# simpleArm-1.net
KiCad netlist of a schematic drawn in EAGLE
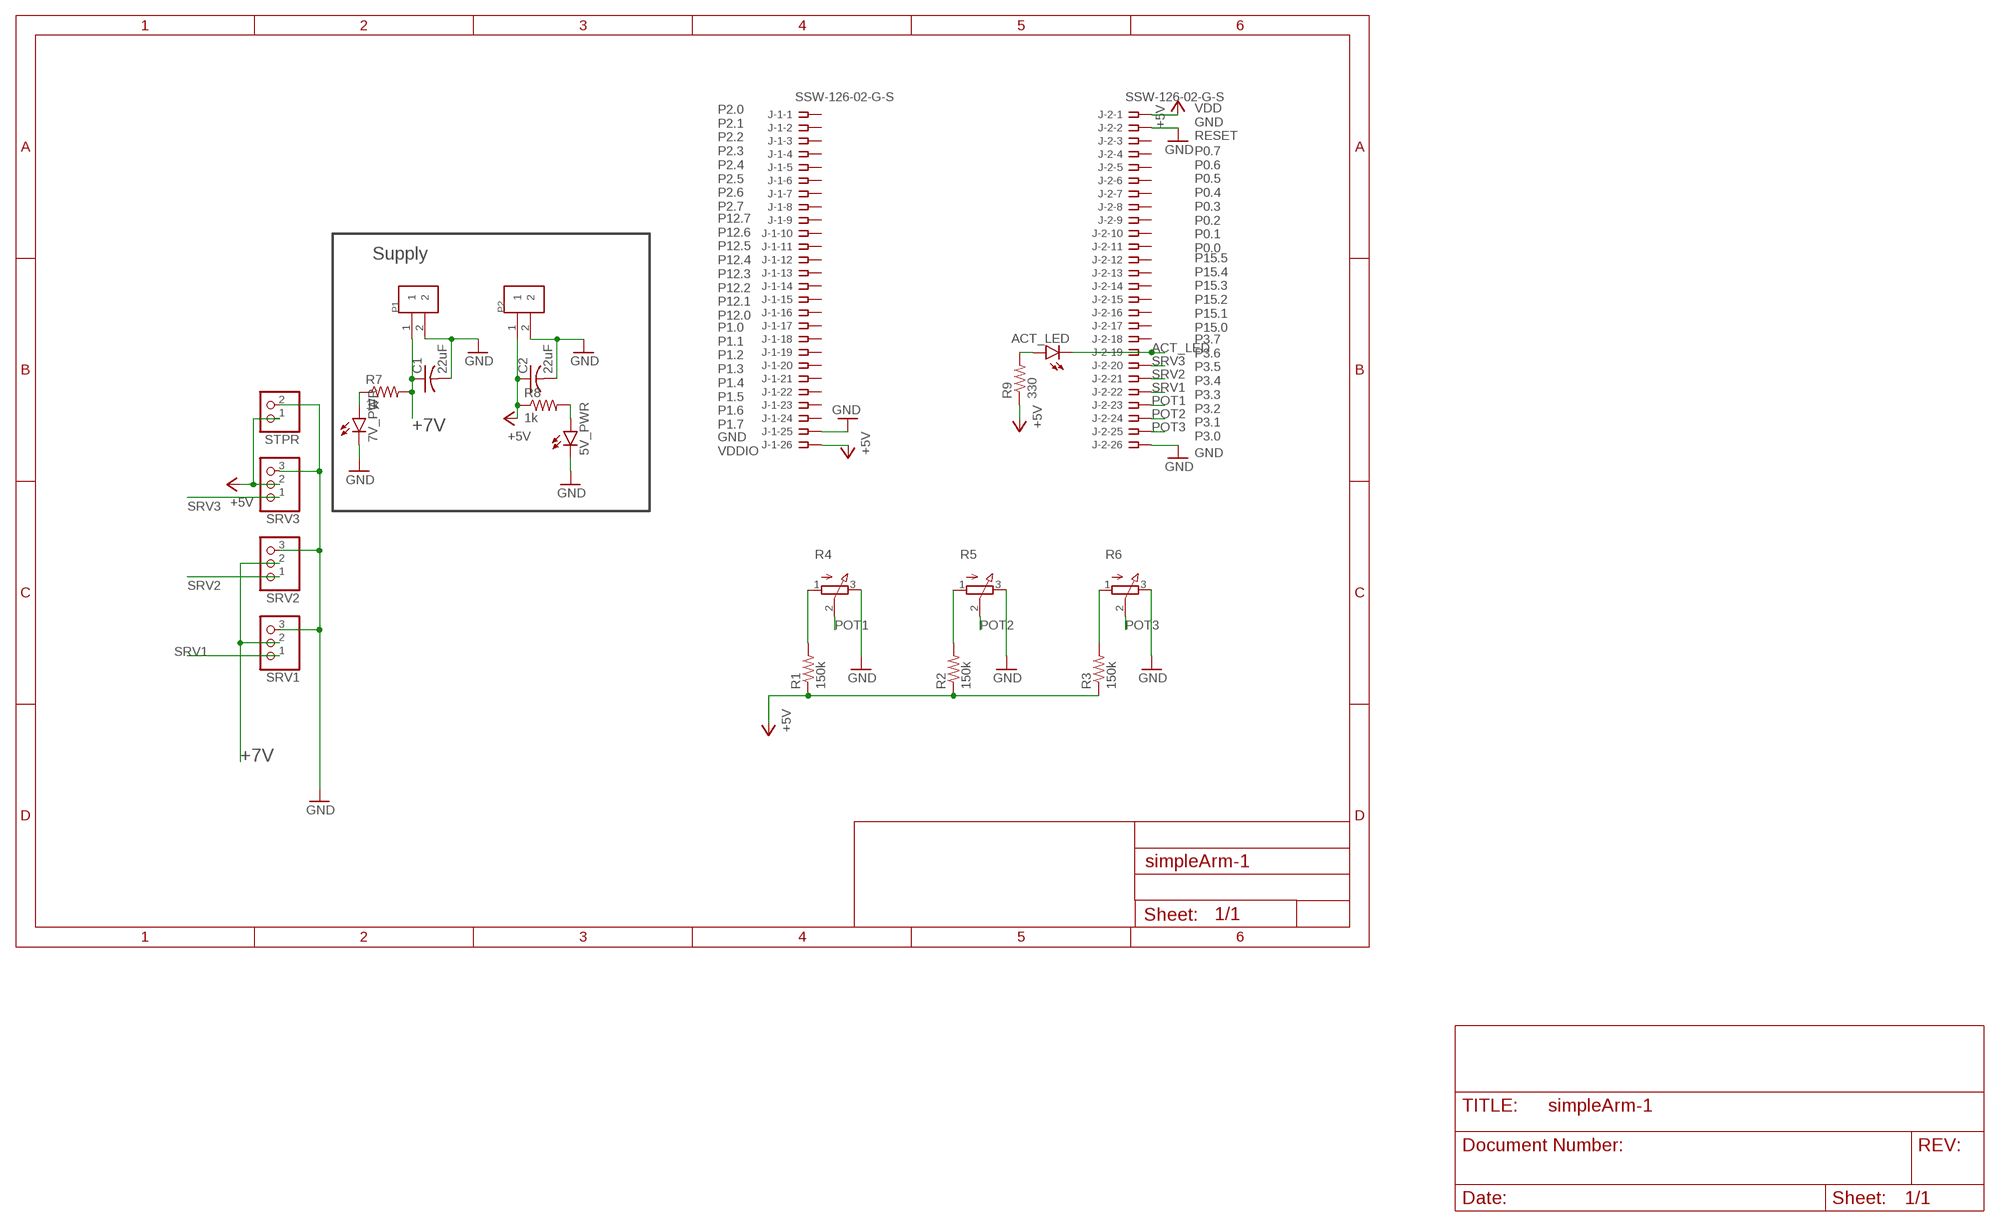
[diagram p0: schematic, sheet 1]

(export (version "E")
  (design (tool "Eeschema 10.0.6"))
  (components
    (comp (ref "5V_PWR")
      (value "LED3MM")
      (footprint "eagle-import:LED3MM")
      (libsource (lib "eagle-import") (part "LED3MM"))
    )
    (comp (ref "7V_PWR")
      (value "LED3MM")
      (footprint "eagle-import:LED3MM")
      (libsource (lib "eagle-import") (part "LED3MM"))
    )
    (comp (ref "ACT_LED")
      (value "LED3MM")
      (footprint "eagle-import:LED3MM")
      (libsource (lib "eagle-import") (part "LED3MM"))
    )
    (comp (ref "C1")
      (value "22uF")
      (footprint "eagle-import:C050-030X075")
      (libsource (lib "eagle-import") (part "C-US050-030X075"))
    )
    (comp (ref "C2")
      (value "22uF")
      (footprint "eagle-import:C050-030X075")
      (libsource (lib "eagle-import") (part "C-US050-030X075"))
    )
    (comp (ref "J-1")
      (value "SSW-126-02-G-S")
      (footprint "eagle-import:SSW-126-02-G-S")
      (fields (field (name "MF") "Samtec Inc."))
      (libsource (lib "eagle-import") (part "SSW-126-02-G-S"))
    )
    (comp (ref "J-2")
      (value "SSW-126-02-G-S")
      (footprint "eagle-import:SSW-126-02-G-S")
      (fields (field (name "MF") "Samtec Inc."))
      (libsource (lib "eagle-import") (part "SSW-126-02-G-S"))
    )
    (comp (ref "P1")
      (value "282837-2")
      (footprint "eagle-import:TE_282837-2")
      (fields (field (name "MF") "TE Connectivity"))
      (libsource (lib "eagle-import") (part "282837-2"))
    )
    (comp (ref "P2")
      (value "282837-2")
      (footprint "eagle-import:TE_282837-2")
      (fields (field (name "MF") "TE Connectivity"))
      (libsource (lib "eagle-import") (part "282837-2"))
    )
    (comp (ref "R1")
      (value "150k")
      (footprint "eagle-import:0204_7")
      (libsource (lib "eagle-import") (part "R-US_0204/7"))
    )
    (comp (ref "R2")
      (value "150k")
      (footprint "eagle-import:0204_7")
      (libsource (lib "eagle-import") (part "R-US_0204/7"))
    )
    (comp (ref "R3")
      (value "150k")
      (footprint "eagle-import:0204_7")
      (libsource (lib "eagle-import") (part "R-US_0204/7"))
    )
    (comp (ref "R4")
      (value "3RP/1610N")
      (footprint "eagle-import:3RP_1610N")
      (libsource (lib "eagle-import") (part "3RP/1610N"))
    )
    (comp (ref "R5")
      (value "3RP/1610N")
      (footprint "eagle-import:3RP_1610N")
      (libsource (lib "eagle-import") (part "3RP/1610N"))
    )
    (comp (ref "R6")
      (value "3RP/1610N")
      (footprint "eagle-import:3RP_1610N")
      (libsource (lib "eagle-import") (part "3RP/1610N"))
    )
    (comp (ref "R7")
      (value "1k")
      (footprint "eagle-import:0204_7")
      (libsource (lib "eagle-import") (part "R-US_0204/7"))
    )
    (comp (ref "R8")
      (value "1k")
      (footprint "eagle-import:0204_7")
      (libsource (lib "eagle-import") (part "R-US_0204/7"))
    )
    (comp (ref "R9")
      (value "330")
      (footprint "eagle-import:0204_7")
      (libsource (lib "eagle-import") (part "R-US_0204/7"))
    )
    (comp (ref "SRV1")
      (value "PINHD-1X3")
      (footprint "eagle-import:1X03")
      (libsource (lib "eagle-import") (part "PINHD-1X3"))
    )
    (comp (ref "SRV2")
      (value "PINHD-1X3")
      (footprint "eagle-import:1X03")
      (libsource (lib "eagle-import") (part "PINHD-1X3"))
    )
    (comp (ref "SRV3")
      (value "PINHD-1X3")
      (footprint "eagle-import:1X03")
      (libsource (lib "eagle-import") (part "PINHD-1X3"))
    )
    (comp (ref "STPR")
      (value "PINHD-1X2")
      (footprint "eagle-import:1X02")
      (libsource (lib "eagle-import") (part "PINHD-1X2"))
    )
  )
  (nets
    (net (code "1") (name "+5V") (class "Default")
      (node (ref "C2") (pin "1") (pinfunction "1_1") (pintype "passive"))
      (node (ref "J-1") (pin "26") (pinfunction "1_26") (pintype "passive"))
      (node (ref "J-2") (pin "1") (pinfunction "1_1") (pintype "passive"))
      (node (ref "P2") (pin "1") (pinfunction "1_1") (pintype "passive"))
      (node (ref "R1") (pin "1") (pinfunction "1_1") (pintype "passive"))
      (node (ref "R2") (pin "1") (pinfunction "1_1") (pintype "passive"))
      (node (ref "R3") (pin "1") (pinfunction "1_1") (pintype "passive"))
      (node (ref "R8") (pin "1") (pinfunction "1_1") (pintype "passive"))
      (node (ref "R9") (pin "1") (pinfunction "1_1") (pintype "passive"))
      (node (ref "SRV3") (pin "2") (pinfunction "2_2") (pintype "passive"))
      (node (ref "STPR") (pin "1") (pinfunction "1_1") (pintype "passive"))
    )
    (net (code "2") (name "/+7V") (class "Default")
      (node (ref "C1") (pin "1") (pinfunction "1_1") (pintype "passive"))
      (node (ref "P1") (pin "1") (pinfunction "1_1") (pintype "passive"))
      (node (ref "R7") (pin "2") (pinfunction "2_2") (pintype "passive"))
      (node (ref "SRV1") (pin "2") (pinfunction "2_2") (pintype "passive"))
      (node (ref "SRV2") (pin "2") (pinfunction "2_2") (pintype "passive"))
    )
    (net (code "3") (name "/ACT_LED") (class "Default")
      (node (ref "ACT_LED") (pin "K") (pinfunction "C_K") (pintype "passive"))
      (node (ref "J-2") (pin "19") (pinfunction "1_19") (pintype "passive"))
    )
    (net (code "4") (name "/POT1") (class "Default")
      (node (ref "J-2") (pin "23") (pinfunction "1_23") (pintype "passive"))
      (node (ref "R4") (pin "2") (pinfunction "S_2") (pintype "passive"))
    )
    (net (code "5") (name "/POT2") (class "Default")
      (node (ref "J-2") (pin "24") (pinfunction "1_24") (pintype "passive"))
      (node (ref "R5") (pin "2") (pinfunction "S_2") (pintype "passive"))
    )
    (net (code "6") (name "/POT3") (class "Default")
      (node (ref "J-2") (pin "25") (pinfunction "1_25") (pintype "passive"))
      (node (ref "R6") (pin "2") (pinfunction "S_2") (pintype "passive"))
    )
    (net (code "7") (name "/SRV1") (class "Default")
      (node (ref "J-2") (pin "22") (pinfunction "1_22") (pintype "passive"))
      (node (ref "SRV1") (pin "1") (pinfunction "1_1") (pintype "passive"))
    )
    (net (code "8") (name "/SRV2") (class "Default")
      (node (ref "J-2") (pin "21") (pinfunction "1_21") (pintype "passive"))
      (node (ref "SRV2") (pin "1") (pinfunction "1_1") (pintype "passive"))
    )
    (net (code "9") (name "/SRV3") (class "Default")
      (node (ref "J-2") (pin "20") (pinfunction "1_20") (pintype "passive"))
      (node (ref "SRV3") (pin "1") (pinfunction "1_1") (pintype "passive"))
    )
    (net (code "10") (name "GND") (class "Default")
      (node (ref "5V_PWR") (pin "K") (pinfunction "C_K") (pintype "passive"))
      (node (ref "7V_PWR") (pin "K") (pinfunction "C_K") (pintype "passive"))
      (node (ref "C1") (pin "2") (pinfunction "2_2") (pintype "passive"))
      (node (ref "C2") (pin "2") (pinfunction "2_2") (pintype "passive"))
      (node (ref "J-1") (pin "25") (pinfunction "1_25") (pintype "passive"))
      (node (ref "J-2") (pin "2") (pinfunction "1_2") (pintype "passive"))
      (node (ref "J-2") (pin "26") (pinfunction "1_26") (pintype "passive"))
      (node (ref "P1") (pin "2") (pinfunction "2_2") (pintype "passive"))
      (node (ref "P2") (pin "2") (pinfunction "2_2") (pintype "passive"))
      (node (ref "R4") (pin "3") (pinfunction "E_3") (pintype "passive"))
      (node (ref "R5") (pin "3") (pinfunction "E_3") (pintype "passive"))
      (node (ref "R6") (pin "3") (pinfunction "E_3") (pintype "passive"))
      (node (ref "SRV1") (pin "3") (pinfunction "3_3") (pintype "passive"))
      (node (ref "SRV2") (pin "3") (pinfunction "3_3") (pintype "passive"))
      (node (ref "SRV3") (pin "3") (pinfunction "3_3") (pintype "passive"))
      (node (ref "STPR") (pin "2") (pinfunction "2_2") (pintype "passive"))
    )
    (net (code "11") (name "Net-(5V_PWR-PadA)") (class "Default")
      (node (ref "5V_PWR") (pin "A") (pinfunction "A_A") (pintype "passive"))
      (node (ref "R8") (pin "2") (pinfunction "2_2") (pintype "passive"))
    )
    (net (code "12") (name "Net-(7V_PWR-PadA)") (class "Default")
      (node (ref "7V_PWR") (pin "A") (pinfunction "A_A") (pintype "passive"))
      (node (ref "R7") (pin "1") (pinfunction "1_1") (pintype "passive"))
    )
    (net (code "13") (name "Net-(ACT_LED-PadA)") (class "Default")
      (node (ref "ACT_LED") (pin "A") (pinfunction "A_A") (pintype "passive"))
      (node (ref "R9") (pin "2") (pinfunction "2_2") (pintype "passive"))
    )
    (net (code "14") (name "Net-(R4-A)") (class "Default")
      (node (ref "R1") (pin "2") (pinfunction "2_2") (pintype "passive"))
      (node (ref "R4") (pin "1") (pinfunction "A_1") (pintype "passive"))
    )
    (net (code "15") (name "Net-(R5-A)") (class "Default")
      (node (ref "R2") (pin "2") (pinfunction "2_2") (pintype "passive"))
      (node (ref "R5") (pin "1") (pinfunction "A_1") (pintype "passive"))
    )
    (net (code "16") (name "Net-(R6-A)") (class "Default")
      (node (ref "R3") (pin "2") (pinfunction "2_2") (pintype "passive"))
      (node (ref "R6") (pin "1") (pinfunction "A_1") (pintype "passive"))
    )
    (net (code "17") (name "unconnected-(J-1-Pad1)") (class "Default")
      (node (ref "J-1") (pin "1") (pinfunction "1_1") (pintype "passive"))
    )
    (net (code "18") (name "unconnected-(J-1B-1-Pad10)") (class "Default")
      (node (ref "J-1") (pin "10") (pinfunction "1_10") (pintype "passive"))
    )
    (net (code "19") (name "unconnected-(J-1C-1-Pad11)") (class "Default")
      (node (ref "J-1") (pin "11") (pinfunction "1_11") (pintype "passive"))
    )
    (net (code "20") (name "unconnected-(J-1D-1-Pad12)") (class "Default")
      (node (ref "J-1") (pin "12") (pinfunction "1_12") (pintype "passive"))
    )
    (net (code "21") (name "unconnected-(J-1E-1-Pad13)") (class "Default")
      (node (ref "J-1") (pin "13") (pinfunction "1_13") (pintype "passive"))
    )
    (net (code "22") (name "unconnected-(J-1F-1-Pad14)") (class "Default")
      (node (ref "J-1") (pin "14") (pinfunction "1_14") (pintype "passive"))
    )
    (net (code "23") (name "unconnected-(J-1G-1-Pad15)") (class "Default")
      (node (ref "J-1") (pin "15") (pinfunction "1_15") (pintype "passive"))
    )
    (net (code "24") (name "unconnected-(J-1H-1-Pad16)") (class "Default")
      (node (ref "J-1") (pin "16") (pinfunction "1_16") (pintype "passive"))
    )
    (net (code "25") (name "unconnected-(J-1I-1-Pad17)") (class "Default")
      (node (ref "J-1") (pin "17") (pinfunction "1_17") (pintype "passive"))
    )
    (net (code "26") (name "unconnected-(J-1J-1-Pad18)") (class "Default")
      (node (ref "J-1") (pin "18") (pinfunction "1_18") (pintype "passive"))
    )
    (net (code "27") (name "unconnected-(J-1K-1-Pad19)") (class "Default")
      (node (ref "J-1") (pin "19") (pinfunction "1_19") (pintype "passive"))
    )
    (net (code "28") (name "unconnected-(J-1L-1-Pad2)") (class "Default")
      (node (ref "J-1") (pin "2") (pinfunction "1_2") (pintype "passive"))
    )
    (net (code "29") (name "unconnected-(J-1M-1-Pad20)") (class "Default")
      (node (ref "J-1") (pin "20") (pinfunction "1_20") (pintype "passive"))
    )
    (net (code "30") (name "unconnected-(J-1N-1-Pad21)") (class "Default")
      (node (ref "J-1") (pin "21") (pinfunction "1_21") (pintype "passive"))
    )
    (net (code "31") (name "unconnected-(J-1O-1-Pad22)") (class "Default")
      (node (ref "J-1") (pin "22") (pinfunction "1_22") (pintype "passive"))
    )
    (net (code "32") (name "unconnected-(J-1P-1-Pad23)") (class "Default")
      (node (ref "J-1") (pin "23") (pinfunction "1_23") (pintype "passive"))
    )
    (net (code "33") (name "unconnected-(J-1Q-1-Pad24)") (class "Default")
      (node (ref "J-1") (pin "24") (pinfunction "1_24") (pintype "passive"))
    )
    (net (code "34") (name "unconnected-(J-1T-1-Pad3)") (class "Default")
      (node (ref "J-1") (pin "3") (pinfunction "1_3") (pintype "passive"))
    )
    (net (code "35") (name "unconnected-(J-1U-1-Pad4)") (class "Default")
      (node (ref "J-1") (pin "4") (pinfunction "1_4") (pintype "passive"))
    )
    (net (code "36") (name "unconnected-(J-1V-1-Pad5)") (class "Default")
      (node (ref "J-1") (pin "5") (pinfunction "1_5") (pintype "passive"))
    )
    (net (code "37") (name "unconnected-(J-1W-1-Pad6)") (class "Default")
      (node (ref "J-1") (pin "6") (pinfunction "1_6") (pintype "passive"))
    )
    (net (code "38") (name "unconnected-(J-1X-1-Pad7)") (class "Default")
      (node (ref "J-1") (pin "7") (pinfunction "1_7") (pintype "passive"))
    )
    (net (code "39") (name "unconnected-(J-1Y-1-Pad8)") (class "Default")
      (node (ref "J-1") (pin "8") (pinfunction "1_8") (pintype "passive"))
    )
    (net (code "40") (name "unconnected-(J-1Z-1-Pad9)") (class "Default")
      (node (ref "J-1") (pin "9") (pinfunction "1_9") (pintype "passive"))
    )
    (net (code "41") (name "unconnected-(J-2B-1-Pad10)") (class "Default")
      (node (ref "J-2") (pin "10") (pinfunction "1_10") (pintype "passive"))
    )
    (net (code "42") (name "unconnected-(J-2C-1-Pad11)") (class "Default")
      (node (ref "J-2") (pin "11") (pinfunction "1_11") (pintype "passive"))
    )
    (net (code "43") (name "unconnected-(J-2D-1-Pad12)") (class "Default")
      (node (ref "J-2") (pin "12") (pinfunction "1_12") (pintype "passive"))
    )
    (net (code "44") (name "unconnected-(J-2E-1-Pad13)") (class "Default")
      (node (ref "J-2") (pin "13") (pinfunction "1_13") (pintype "passive"))
    )
    (net (code "45") (name "unconnected-(J-2F-1-Pad14)") (class "Default")
      (node (ref "J-2") (pin "14") (pinfunction "1_14") (pintype "passive"))
    )
    (net (code "46") (name "unconnected-(J-2G-1-Pad15)") (class "Default")
      (node (ref "J-2") (pin "15") (pinfunction "1_15") (pintype "passive"))
    )
    (net (code "47") (name "unconnected-(J-2H-1-Pad16)") (class "Default")
      (node (ref "J-2") (pin "16") (pinfunction "1_16") (pintype "passive"))
    )
    (net (code "48") (name "unconnected-(J-2I-1-Pad17)") (class "Default")
      (node (ref "J-2") (pin "17") (pinfunction "1_17") (pintype "passive"))
    )
    (net (code "49") (name "unconnected-(J-2J-1-Pad18)") (class "Default")
      (node (ref "J-2") (pin "18") (pinfunction "1_18") (pintype "passive"))
    )
    (net (code "50") (name "unconnected-(J-2T-1-Pad3)") (class "Default")
      (node (ref "J-2") (pin "3") (pinfunction "1_3") (pintype "passive"))
    )
    (net (code "51") (name "unconnected-(J-2U-1-Pad4)") (class "Default")
      (node (ref "J-2") (pin "4") (pinfunction "1_4") (pintype "passive"))
    )
    (net (code "52") (name "unconnected-(J-2V-1-Pad5)") (class "Default")
      (node (ref "J-2") (pin "5") (pinfunction "1_5") (pintype "passive"))
    )
    (net (code "53") (name "unconnected-(J-2W-1-Pad6)") (class "Default")
      (node (ref "J-2") (pin "6") (pinfunction "1_6") (pintype "passive"))
    )
    (net (code "54") (name "unconnected-(J-2X-1-Pad7)") (class "Default")
      (node (ref "J-2") (pin "7") (pinfunction "1_7") (pintype "passive"))
    )
    (net (code "55") (name "unconnected-(J-2Y-1-Pad8)") (class "Default")
      (node (ref "J-2") (pin "8") (pinfunction "1_8") (pintype "passive"))
    )
    (net (code "56") (name "unconnected-(J-2Z-1-Pad9)") (class "Default")
      (node (ref "J-2") (pin "9") (pinfunction "1_9") (pintype "passive"))
    )
  )
)
